# ESC_D.net
KiCad netlist of a schematic drawn in Altium Designer
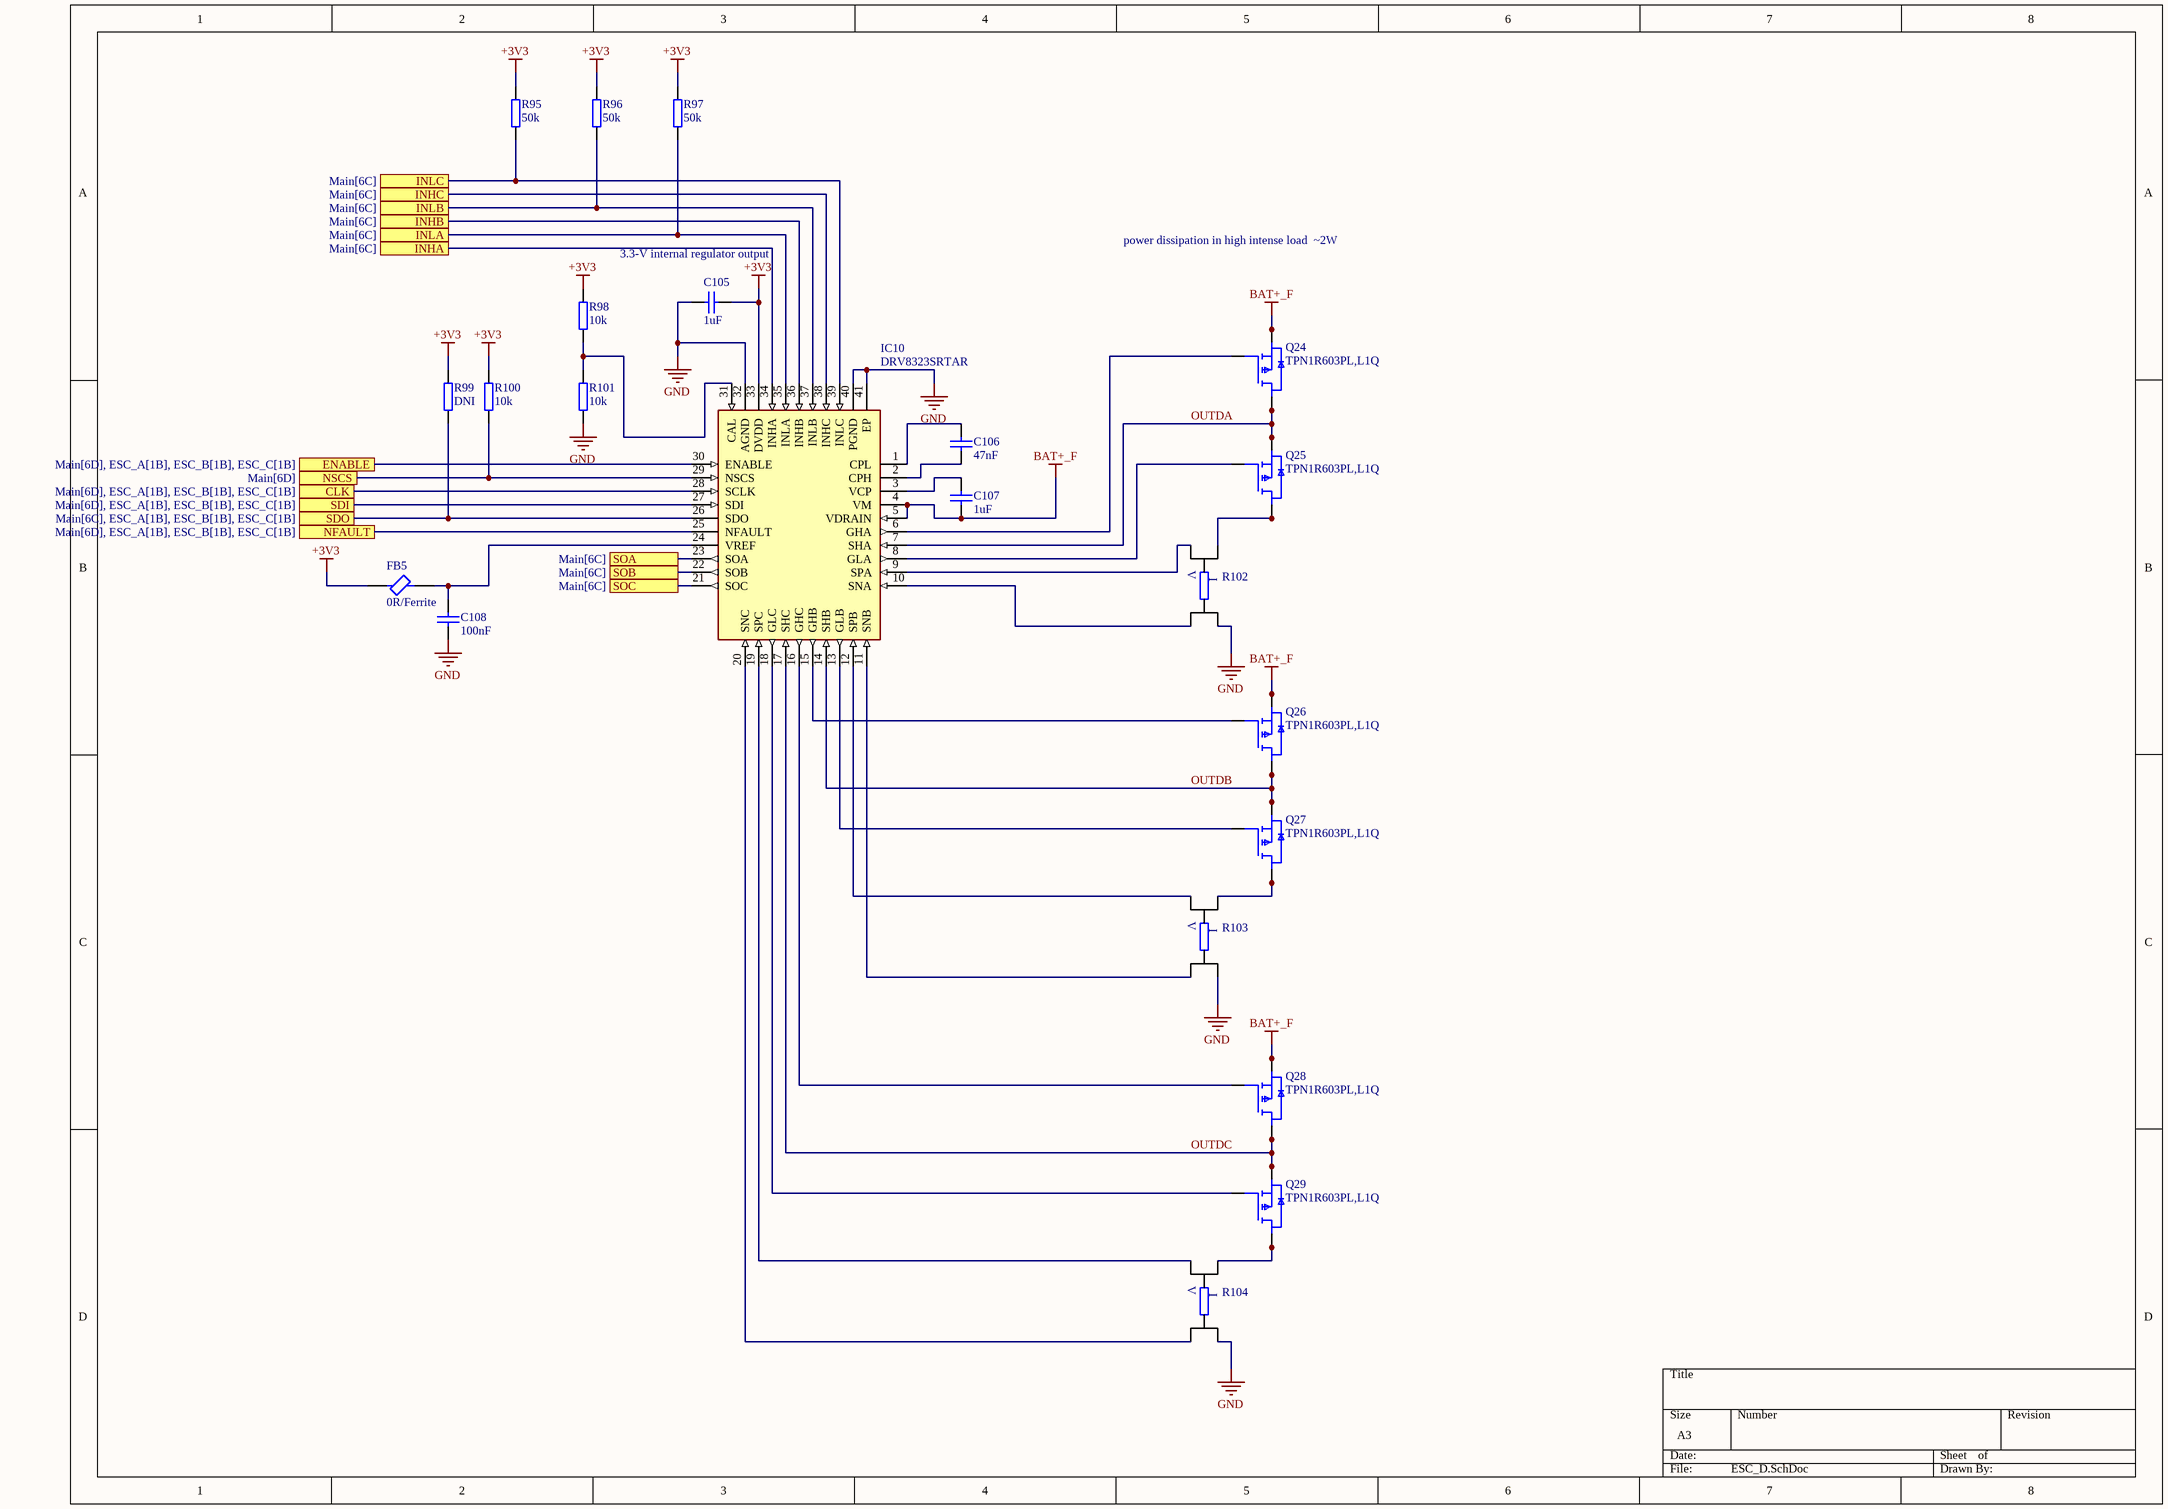
[diagram p0: ESC_D.SchDoc]

(export (version "E")
  (design (tool "Eeschema 10.0.6"))
  (components
    (comp (ref "C105")
      (value "1uF")
      (footprint "CAP0402")
      (fields
        (field (name "VOLTAGE") "50V")
        (field (name "MANUFACTURER_PART_NUMBER") "GRM155R61H105KE05J")
        (field (name "Comment") "Cap0402")
      )
      (libsource (lib "capacitorsSMD") (part "Cap0402"))
    )
    (comp (ref "C106")
      (value "47nF")
      (footprint "CAP0603")
      (description "50V")
      (fields (field (name "Comment") "Cap0603") (field (name "PUBLISHER") "Altium Limited"))
      (libsource (lib "capacitorsSMD") (part "CapSMD0603"))
    )
    (comp (ref "C107")
      (value "1uF")
      (footprint "CAP0603")
      (description "50V")
      (fields (field (name "Comment") "Cap0603") (field (name "PUBLISHER") "Altium Limited"))
      (libsource (lib "capacitorsSMD") (part "CapSMD0603"))
    )
    (comp (ref "C108")
      (value "100nF")
      (footprint "CAP0402")
      (fields
        (field (name "VOLTAGE") "50V")
        (field (name "MANUFACTURER_PART_NUMBER") "GRM155R71H104ME14D")
        (field (name "Comment") "Cap0402")
      )
      (libsource (lib "capacitorsSMD") (part "Cap0402"))
    )
    (comp (ref "FB5")
      (value "0R/Ferrite")
      (footprint "SamacSys:NFZ15SG152SN10B")
      (description "Ferrite Bead")
      (fields
        (field (name "MANUFACTURER_PART_NUMBER") "BLM15PE471SH1D")
        (field (name "MOUSER PART NUMBER") "81-BLM15PE471SH1D")
      )
      (libsource (lib "SamacSys") (part "BLM15PE471SH1D"))
    )
    (comp (ref "IC10")
      (value "DRV8323SRTAR")
      (footprint "SamacSys:QFN50P600X600X80-41N-D")
      (description "Integrated Circuit")
      (fields (field (name "MOUSER PART NUMBER") "595-DRV8323SRTAR"))
      (libsource (lib "*") (part "DRV8323SRTAR"))
    )
    (comp (ref "Q24")
      (value "TPN1R603PL,L1Q")
      (footprint "SamacSys:TPN1R603PLL1Q")
      (description "MOSFET (N-Channel)")
      (fields (field (name "MOUSER PART NUMBER") "757-TPN1R603PLL1Q"))
      (libsource (lib "SamacSys") (part "TPN1R603PL,L1Q"))
    )
    (comp (ref "Q25")
      (value "TPN1R603PL,L1Q")
      (footprint "SamacSys:TPN1R603PLL1Q")
      (description "MOSFET (N-Channel)")
      (fields (field (name "MOUSER PART NUMBER") "757-TPN1R603PLL1Q"))
      (libsource (lib "SamacSys") (part "TPN1R603PL,L1Q"))
    )
    (comp (ref "Q26")
      (value "TPN1R603PL,L1Q")
      (footprint "SamacSys:TPN1R603PLL1Q")
      (description "MOSFET (N-Channel)")
      (fields (field (name "MOUSER PART NUMBER") "757-TPN1R603PLL1Q"))
      (libsource (lib "SamacSys") (part "TPN1R603PL,L1Q"))
    )
    (comp (ref "Q27")
      (value "TPN1R603PL,L1Q")
      (footprint "SamacSys:TPN1R603PLL1Q")
      (description "MOSFET (N-Channel)")
      (fields (field (name "MOUSER PART NUMBER") "757-TPN1R603PLL1Q"))
      (libsource (lib "SamacSys") (part "TPN1R603PL,L1Q"))
    )
    (comp (ref "Q28")
      (value "TPN1R603PL,L1Q")
      (footprint "SamacSys:TPN1R603PLL1Q")
      (description "MOSFET (N-Channel)")
      (fields (field (name "MOUSER PART NUMBER") "757-TPN1R603PLL1Q"))
      (libsource (lib "SamacSys") (part "TPN1R603PL,L1Q"))
    )
    (comp (ref "Q29")
      (value "TPN1R603PL,L1Q")
      (footprint "SamacSys:TPN1R603PLL1Q")
      (description "MOSFET (N-Channel)")
      (fields (field (name "MOUSER PART NUMBER") "757-TPN1R603PLL1Q"))
      (libsource (lib "SamacSys") (part "TPN1R603PL,L1Q"))
    )
    (comp (ref "R95")
      (value "50k")
      (footprint "RES0402")
      (fields (field (name "MANUFACTURER_PART_NUMBER") "TNPW040249K9DEED") (field (name "Comment") "Res0402"))
      (libsource (lib "resistorSMD") (part "Res0402"))
    )
    (comp (ref "R96")
      (value "50k")
      (footprint "RES0402")
      (fields (field (name "MANUFACTURER_PART_NUMBER") "TNPW040249K9DEED") (field (name "Comment") "Res0402"))
      (libsource (lib "resistorSMD") (part "Res0402"))
    )
    (comp (ref "R97")
      (value "50k")
      (footprint "RES0402")
      (fields (field (name "MANUFACTURER_PART_NUMBER") "TNPW040249K9DEED") (field (name "Comment") "Res0402"))
      (libsource (lib "resistorSMD") (part "Res0402"))
    )
    (comp (ref "R98")
      (value "10k")
      (footprint "RES0402")
      (fields (field (name "MANUFACTURER_PART_NUMBER") "ERA-2AED103X") (field (name "Comment") "Res0402"))
      (libsource (lib "resistorSMD") (part "Res0402"))
    )
    (comp (ref "R99")
      (value "DNI")
      (footprint "RES0402")
      (fields (field (name "Comment") "Res0402"))
      (libsource (lib "resistorSMD") (part "Res0402"))
    )
    (comp (ref "R100")
      (value "10k")
      (footprint "RES0402")
      (fields (field (name "MANUFACTURER_PART_NUMBER") "ERA-2AED103X") (field (name "Comment") "Res0402"))
      (libsource (lib "resistorSMD") (part "Res0402"))
    )
    (comp (ref "R101")
      (value "10k")
      (footprint "RES0402")
      (fields (field (name "MANUFACTURER_PART_NUMBER") "ERA-2AED103X") (field (name "Comment") "Res0402"))
      (libsource (lib "resistorSMD") (part "Res0402"))
    )
    (comp (ref "R102")
      (value "WSK12161L000FEA")
      (footprint "SamacSys:WSK12161L000FEA")
      (description "Resistor")
      (fields
        (field (name "MANUFACTURER_PART_NUMBER") "WSK1216L5000FEA")
        (field (name "MOUSER PART NUMBER") "71-WSK1216L5000FEA")
      )
      (libsource (lib "SamacSys") (part "WSK1216L5000FEA"))
    )
    (comp (ref "R103")
      (value "WSK12161L000FEA")
      (footprint "SamacSys:WSK12161L000FEA")
      (description "Resistor")
      (fields
        (field (name "MANUFACTURER_PART_NUMBER") "WSK1216L5000FEA")
        (field (name "MOUSER PART NUMBER") "71-WSK1216L5000FEA")
      )
      (libsource (lib "SamacSys") (part "WSK1216L5000FEA"))
    )
    (comp (ref "R104")
      (value "WSK12161L000FEA")
      (footprint "SamacSys:WSK12161L000FEA")
      (description "Resistor")
      (fields
        (field (name "MANUFACTURER_PART_NUMBER") "WSK1216L5000FEA")
        (field (name "MOUSER PART NUMBER") "71-WSK1216L5000FEA")
      )
      (libsource (lib "SamacSys") (part "WSK1216L5000FEA"))
    )
  )
  (nets
    (net (code "1") (name "+3V3") (class "Default")
      (node (ref "C105") (pin "2") (pinfunction "2_2") (pintype "passive"))
      (node (ref "FB5") (pin "1") (pinfunction "1_1") (pintype "passive"))
      (node (ref "IC10") (pin "33") (pinfunction "DVDD_33") (pintype "power_in"))
      (node (ref "R100") (pin "2") (pinfunction "2_2") (pintype "passive"))
      (node (ref "R95") (pin "2") (pinfunction "2_2") (pintype "passive"))
      (node (ref "R96") (pin "2") (pinfunction "2_2") (pintype "passive"))
      (node (ref "R97") (pin "2") (pinfunction "2_2") (pintype "passive"))
      (node (ref "R98") (pin "2") (pinfunction "2_2") (pintype "passive"))
      (node (ref "R99") (pin "2") (pinfunction "2_2") (pintype "passive"))
    )
    (net (code "2") (name "/CLK") (class "Default")
      (node (ref "IC10") (pin "28") (pinfunction "SCLK_28") (pintype "input"))
    )
    (net (code "3") (name "/ENABLE") (class "Default")
      (node (ref "IC10") (pin "30") (pinfunction "ENABLE_30") (pintype "input"))
    )
    (net (code "4") (name "/INHA") (class "Default")
      (node (ref "IC10") (pin "34") (pinfunction "INHA_34") (pintype "input"))
    )
    (net (code "5") (name "/INHB") (class "Default")
      (node (ref "IC10") (pin "36") (pinfunction "INHB_36") (pintype "input"))
    )
    (net (code "6") (name "/INHC") (class "Default")
      (node (ref "IC10") (pin "38") (pinfunction "INHC_38") (pintype "input"))
    )
    (net (code "7") (name "/INLA") (class "Default")
      (node (ref "IC10") (pin "35") (pinfunction "INLA_35") (pintype "input"))
      (node (ref "R97") (pin "1") (pinfunction "1_1") (pintype "passive"))
    )
    (net (code "8") (name "/INLB") (class "Default")
      (node (ref "IC10") (pin "37") (pinfunction "INLB_37") (pintype "input"))
      (node (ref "R96") (pin "1") (pinfunction "1_1") (pintype "passive"))
    )
    (net (code "9") (name "/INLC") (class "Default")
      (node (ref "IC10") (pin "39") (pinfunction "INLC_39") (pintype "input"))
      (node (ref "R95") (pin "1") (pinfunction "1_1") (pintype "passive"))
    )
    (net (code "10") (name "/NFAULT") (class "Default")
      (node (ref "IC10") (pin "25") (pinfunction "NFAULT_25") (pintype "passive"))
    )
    (net (code "11") (name "/NSCS") (class "Default")
      (node (ref "IC10") (pin "29") (pinfunction "NSCS_29") (pintype "input"))
      (node (ref "R100") (pin "1") (pinfunction "1_1") (pintype "passive"))
    )
    (net (code "12") (name "/OUTDA") (class "Default")
      (node (ref "IC10") (pin "7") (pinfunction "SHA_7") (pintype "input"))
      (node (ref "Q24") (pin "5") (pinfunction "D_1_5") (pintype "passive"))
      (node (ref "Q24") (pin "6") (pinfunction "D_2_6") (pintype "passive"))
      (node (ref "Q24") (pin "7") (pinfunction "D_3_7") (pintype "passive"))
      (node (ref "Q24") (pin "8") (pinfunction "D_4_8") (pintype "passive"))
      (node (ref "Q24") (pin "9") (pinfunction "D_4_9") (pintype "passive"))
      (node (ref "Q25") (pin "1") (pinfunction "S_1_1") (pintype "passive"))
      (node (ref "Q25") (pin "2") (pinfunction "S_2_2") (pintype "passive"))
      (node (ref "Q25") (pin "3") (pinfunction "S_3_3") (pintype "passive"))
    )
    (net (code "13") (name "/OUTDB") (class "Default")
      (node (ref "IC10") (pin "14") (pinfunction "SHB_14") (pintype "input"))
      (node (ref "Q26") (pin "5") (pinfunction "D_1_5") (pintype "passive"))
      (node (ref "Q26") (pin "6") (pinfunction "D_2_6") (pintype "passive"))
      (node (ref "Q26") (pin "7") (pinfunction "D_3_7") (pintype "passive"))
      (node (ref "Q26") (pin "8") (pinfunction "D_4_8") (pintype "passive"))
      (node (ref "Q26") (pin "9") (pinfunction "D_4_9") (pintype "passive"))
      (node (ref "Q27") (pin "1") (pinfunction "S_1_1") (pintype "passive"))
      (node (ref "Q27") (pin "2") (pinfunction "S_2_2") (pintype "passive"))
      (node (ref "Q27") (pin "3") (pinfunction "S_3_3") (pintype "passive"))
    )
    (net (code "14") (name "/OUTDC") (class "Default")
      (node (ref "IC10") (pin "17") (pinfunction "SHC_17") (pintype "input"))
      (node (ref "Q28") (pin "5") (pinfunction "D_1_5") (pintype "passive"))
      (node (ref "Q28") (pin "6") (pinfunction "D_2_6") (pintype "passive"))
      (node (ref "Q28") (pin "7") (pinfunction "D_3_7") (pintype "passive"))
      (node (ref "Q28") (pin "8") (pinfunction "D_4_8") (pintype "passive"))
      (node (ref "Q28") (pin "9") (pinfunction "D_4_9") (pintype "passive"))
      (node (ref "Q29") (pin "1") (pinfunction "S_1_1") (pintype "passive"))
      (node (ref "Q29") (pin "2") (pinfunction "S_2_2") (pintype "passive"))
      (node (ref "Q29") (pin "3") (pinfunction "S_3_3") (pintype "passive"))
    )
    (net (code "15") (name "/SDI") (class "Default")
      (node (ref "IC10") (pin "27") (pinfunction "SDI_27") (pintype "input"))
    )
    (net (code "16") (name "/SDO") (class "Default")
      (node (ref "IC10") (pin "26") (pinfunction "SDO_26") (pintype "passive"))
      (node (ref "R99") (pin "1") (pinfunction "1_1") (pintype "passive"))
    )
    (net (code "17") (name "/SOA") (class "Default")
      (node (ref "IC10") (pin "23") (pinfunction "SOA_23") (pintype "output"))
    )
    (net (code "18") (name "/SOB") (class "Default")
      (node (ref "IC10") (pin "22") (pinfunction "SOB_22") (pintype "output"))
    )
    (net (code "19") (name "/SOC") (class "Default")
      (node (ref "IC10") (pin "21") (pinfunction "SOC_21") (pintype "output"))
    )
    (net (code "20") (name "BAT+_F") (class "Default")
      (node (ref "C107") (pin "1") (pinfunction "1_1") (pintype "passive"))
      (node (ref "IC10") (pin "4") (pinfunction "VM_4") (pintype "power_in"))
      (node (ref "IC10") (pin "5") (pinfunction "VDRAIN_5") (pintype "input"))
      (node (ref "Q24") (pin "1") (pinfunction "S_1_1") (pintype "passive"))
      (node (ref "Q24") (pin "2") (pinfunction "S_2_2") (pintype "passive"))
      (node (ref "Q24") (pin "3") (pinfunction "S_3_3") (pintype "passive"))
      (node (ref "Q26") (pin "1") (pinfunction "S_1_1") (pintype "passive"))
      (node (ref "Q26") (pin "2") (pinfunction "S_2_2") (pintype "passive"))
      (node (ref "Q26") (pin "3") (pinfunction "S_3_3") (pintype "passive"))
      (node (ref "Q28") (pin "1") (pinfunction "S_1_1") (pintype "passive"))
      (node (ref "Q28") (pin "2") (pinfunction "S_2_2") (pintype "passive"))
      (node (ref "Q28") (pin "3") (pinfunction "S_3_3") (pintype "passive"))
    )
    (net (code "21") (name "GND") (class "Default")
      (node (ref "C105") (pin "1") (pinfunction "1_1") (pintype "passive"))
      (node (ref "C108") (pin "1") (pinfunction "1_1") (pintype "passive"))
      (node (ref "IC10") (pin "32") (pinfunction "AGND_32") (pintype "power_in"))
      (node (ref "IC10") (pin "40") (pinfunction "PGND_40") (pintype "power_in"))
      (node (ref "IC10") (pin "41") (pinfunction "EP_41") (pintype "power_in"))
      (node (ref "R101") (pin "1") (pinfunction "1_1") (pintype "passive"))
      (node (ref "R102") (pin "4") (pinfunction "4_4") (pintype "passive"))
      (node (ref "R103") (pin "4") (pinfunction "4_4") (pintype "passive"))
      (node (ref "R104") (pin "4") (pinfunction "4_4") (pintype "passive"))
    )
    (net (code "22") (name "Net-(IC10-CAL)") (class "Default")
      (node (ref "IC10") (pin "31") (pinfunction "CAL_31") (pintype "input"))
      (node (ref "R101") (pin "2") (pinfunction "2_2") (pintype "passive"))
      (node (ref "R98") (pin "1") (pinfunction "1_1") (pintype "passive"))
    )
    (net (code "23") (name "Net-(IC10-CPH)") (class "Default")
      (node (ref "C106") (pin "1") (pinfunction "1_1") (pintype "passive"))
      (node (ref "IC10") (pin "2") (pinfunction "CPH_2") (pintype "power_in"))
    )
    (net (code "24") (name "Net-(IC10-CPL)") (class "Default")
      (node (ref "C106") (pin "2") (pinfunction "2_2") (pintype "passive"))
      (node (ref "IC10") (pin "1") (pinfunction "CPL_1") (pintype "power_in"))
    )
    (net (code "25") (name "Net-(IC10-GHA)") (class "Default")
      (node (ref "IC10") (pin "6") (pinfunction "GHA_6") (pintype "output"))
      (node (ref "Q24") (pin "4") (pinfunction "G_4") (pintype "passive"))
    )
    (net (code "26") (name "Net-(IC10-GHB)") (class "Default")
      (node (ref "IC10") (pin "15") (pinfunction "GHB_15") (pintype "output"))
      (node (ref "Q26") (pin "4") (pinfunction "G_4") (pintype "passive"))
    )
    (net (code "27") (name "Net-(IC10-GHC)") (class "Default")
      (node (ref "IC10") (pin "16") (pinfunction "GHC_16") (pintype "output"))
      (node (ref "Q28") (pin "4") (pinfunction "G_4") (pintype "passive"))
    )
    (net (code "28") (name "Net-(IC10-GLA)") (class "Default")
      (node (ref "IC10") (pin "8") (pinfunction "GLA_8") (pintype "output"))
      (node (ref "Q25") (pin "4") (pinfunction "G_4") (pintype "passive"))
    )
    (net (code "29") (name "Net-(IC10-GLB)") (class "Default")
      (node (ref "IC10") (pin "13") (pinfunction "GLB_13") (pintype "output"))
      (node (ref "Q27") (pin "4") (pinfunction "G_4") (pintype "passive"))
    )
    (net (code "30") (name "Net-(IC10-GLC)") (class "Default")
      (node (ref "IC10") (pin "18") (pinfunction "GLC_18") (pintype "output"))
      (node (ref "Q29") (pin "4") (pinfunction "G_4") (pintype "passive"))
    )
    (net (code "31") (name "Net-(IC10-SNA)") (class "Default")
      (node (ref "IC10") (pin "10") (pinfunction "SNA_10") (pintype "input"))
      (node (ref "R102") (pin "3") (pinfunction "3_3") (pintype "passive"))
    )
    (net (code "32") (name "Net-(IC10-SNB)") (class "Default")
      (node (ref "IC10") (pin "11") (pinfunction "SNB_11") (pintype "input"))
      (node (ref "R103") (pin "3") (pinfunction "3_3") (pintype "passive"))
    )
    (net (code "33") (name "Net-(IC10-SNC)") (class "Default")
      (node (ref "IC10") (pin "20") (pinfunction "SNC_20") (pintype "input"))
      (node (ref "R104") (pin "3") (pinfunction "3_3") (pintype "passive"))
    )
    (net (code "34") (name "Net-(IC10-SPA)") (class "Default")
      (node (ref "IC10") (pin "9") (pinfunction "SPA_9") (pintype "input"))
      (node (ref "R102") (pin "2") (pinfunction "2_2") (pintype "passive"))
    )
    (net (code "35") (name "Net-(IC10-SPB)") (class "Default")
      (node (ref "IC10") (pin "12") (pinfunction "SPB_12") (pintype "input"))
      (node (ref "R103") (pin "2") (pinfunction "2_2") (pintype "passive"))
    )
    (net (code "36") (name "Net-(IC10-SPC)") (class "Default")
      (node (ref "IC10") (pin "19") (pinfunction "SPC_19") (pintype "input"))
      (node (ref "R104") (pin "2") (pinfunction "2_2") (pintype "passive"))
    )
    (net (code "37") (name "Net-(IC10-VCP)") (class "Default")
      (node (ref "C107") (pin "2") (pinfunction "2_2") (pintype "passive"))
      (node (ref "IC10") (pin "3") (pinfunction "VCP_3") (pintype "power_in"))
    )
    (net (code "38") (name "Net-(IC10-VREF)") (class "Default")
      (node (ref "C108") (pin "2") (pinfunction "2_2") (pintype "passive"))
      (node (ref "FB5") (pin "2") (pinfunction "2_2") (pintype "passive"))
      (node (ref "IC10") (pin "24") (pinfunction "VREF_24") (pintype "power_in"))
    )
    (net (code "39") (name "Net-(Q25-D_1)") (class "Default")
      (node (ref "Q25") (pin "5") (pinfunction "D_1_5") (pintype "passive"))
      (node (ref "Q25") (pin "6") (pinfunction "D_2_6") (pintype "passive"))
      (node (ref "Q25") (pin "7") (pinfunction "D_3_7") (pintype "passive"))
      (node (ref "Q25") (pin "8") (pinfunction "D_4_8") (pintype "passive"))
      (node (ref "Q25") (pin "9") (pinfunction "D_4_9") (pintype "passive"))
      (node (ref "R102") (pin "1") (pinfunction "1_1") (pintype "passive"))
    )
    (net (code "40") (name "Net-(Q27-D_1)") (class "Default")
      (node (ref "Q27") (pin "5") (pinfunction "D_1_5") (pintype "passive"))
      (node (ref "Q27") (pin "6") (pinfunction "D_2_6") (pintype "passive"))
      (node (ref "Q27") (pin "7") (pinfunction "D_3_7") (pintype "passive"))
      (node (ref "Q27") (pin "8") (pinfunction "D_4_8") (pintype "passive"))
      (node (ref "Q27") (pin "9") (pinfunction "D_4_9") (pintype "passive"))
      (node (ref "R103") (pin "1") (pinfunction "1_1") (pintype "passive"))
    )
    (net (code "41") (name "Net-(Q29-D_1)") (class "Default")
      (node (ref "Q29") (pin "5") (pinfunction "D_1_5") (pintype "passive"))
      (node (ref "Q29") (pin "6") (pinfunction "D_2_6") (pintype "passive"))
      (node (ref "Q29") (pin "7") (pinfunction "D_3_7") (pintype "passive"))
      (node (ref "Q29") (pin "8") (pinfunction "D_4_8") (pintype "passive"))
      (node (ref "Q29") (pin "9") (pinfunction "D_4_9") (pintype "passive"))
      (node (ref "R104") (pin "1") (pinfunction "1_1") (pintype "passive"))
    )
  )
)
